# main_board.net
KiCad netlist of a schematic drawn in EAGLE
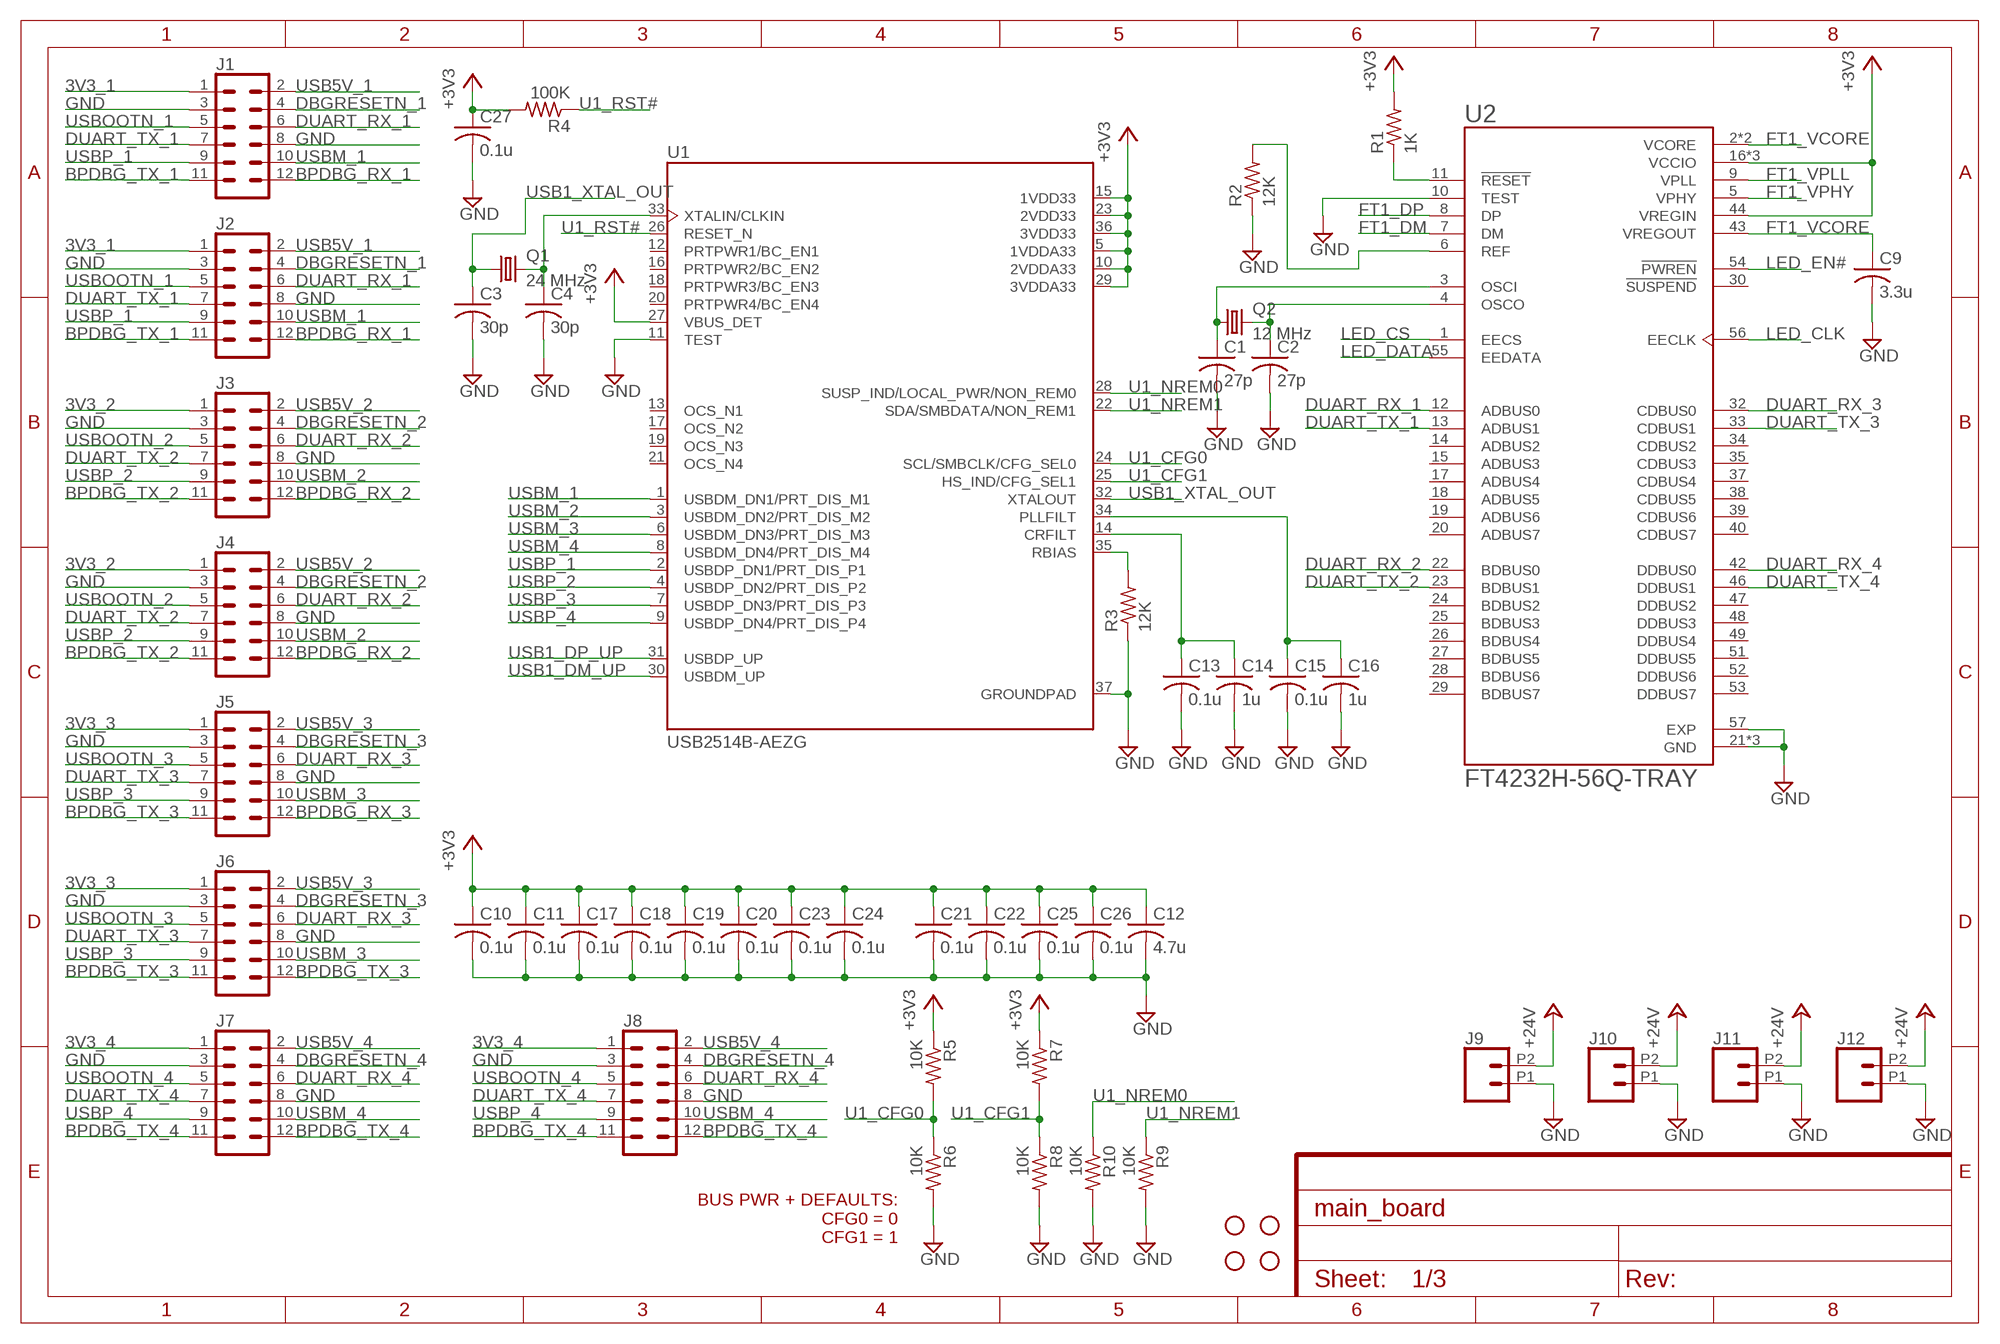
[diagram p0: schematic, sheet 1]
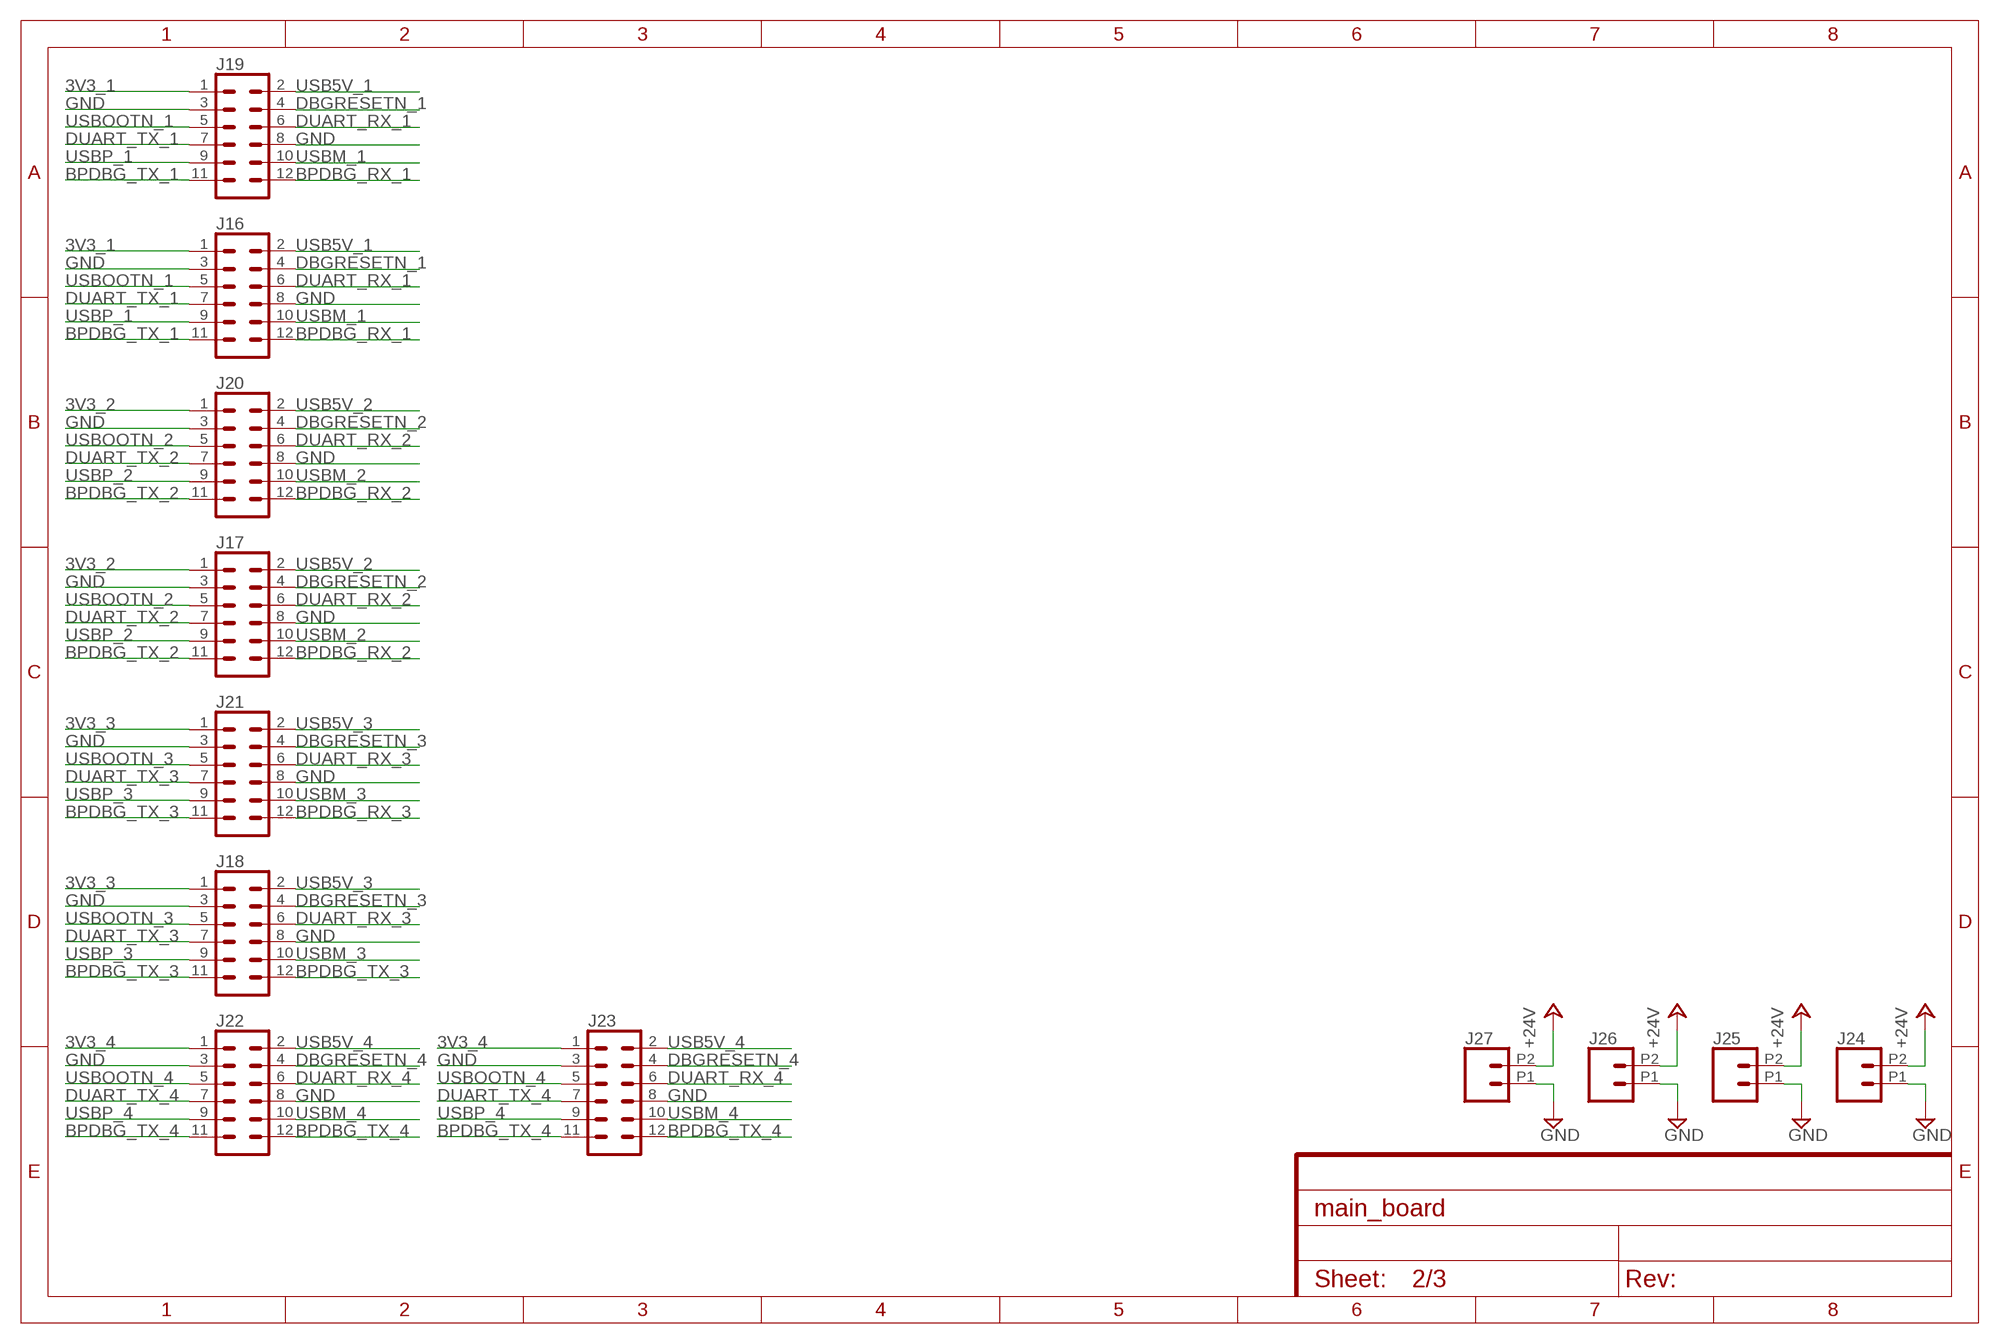
[diagram p1: schematic, sheet 2]
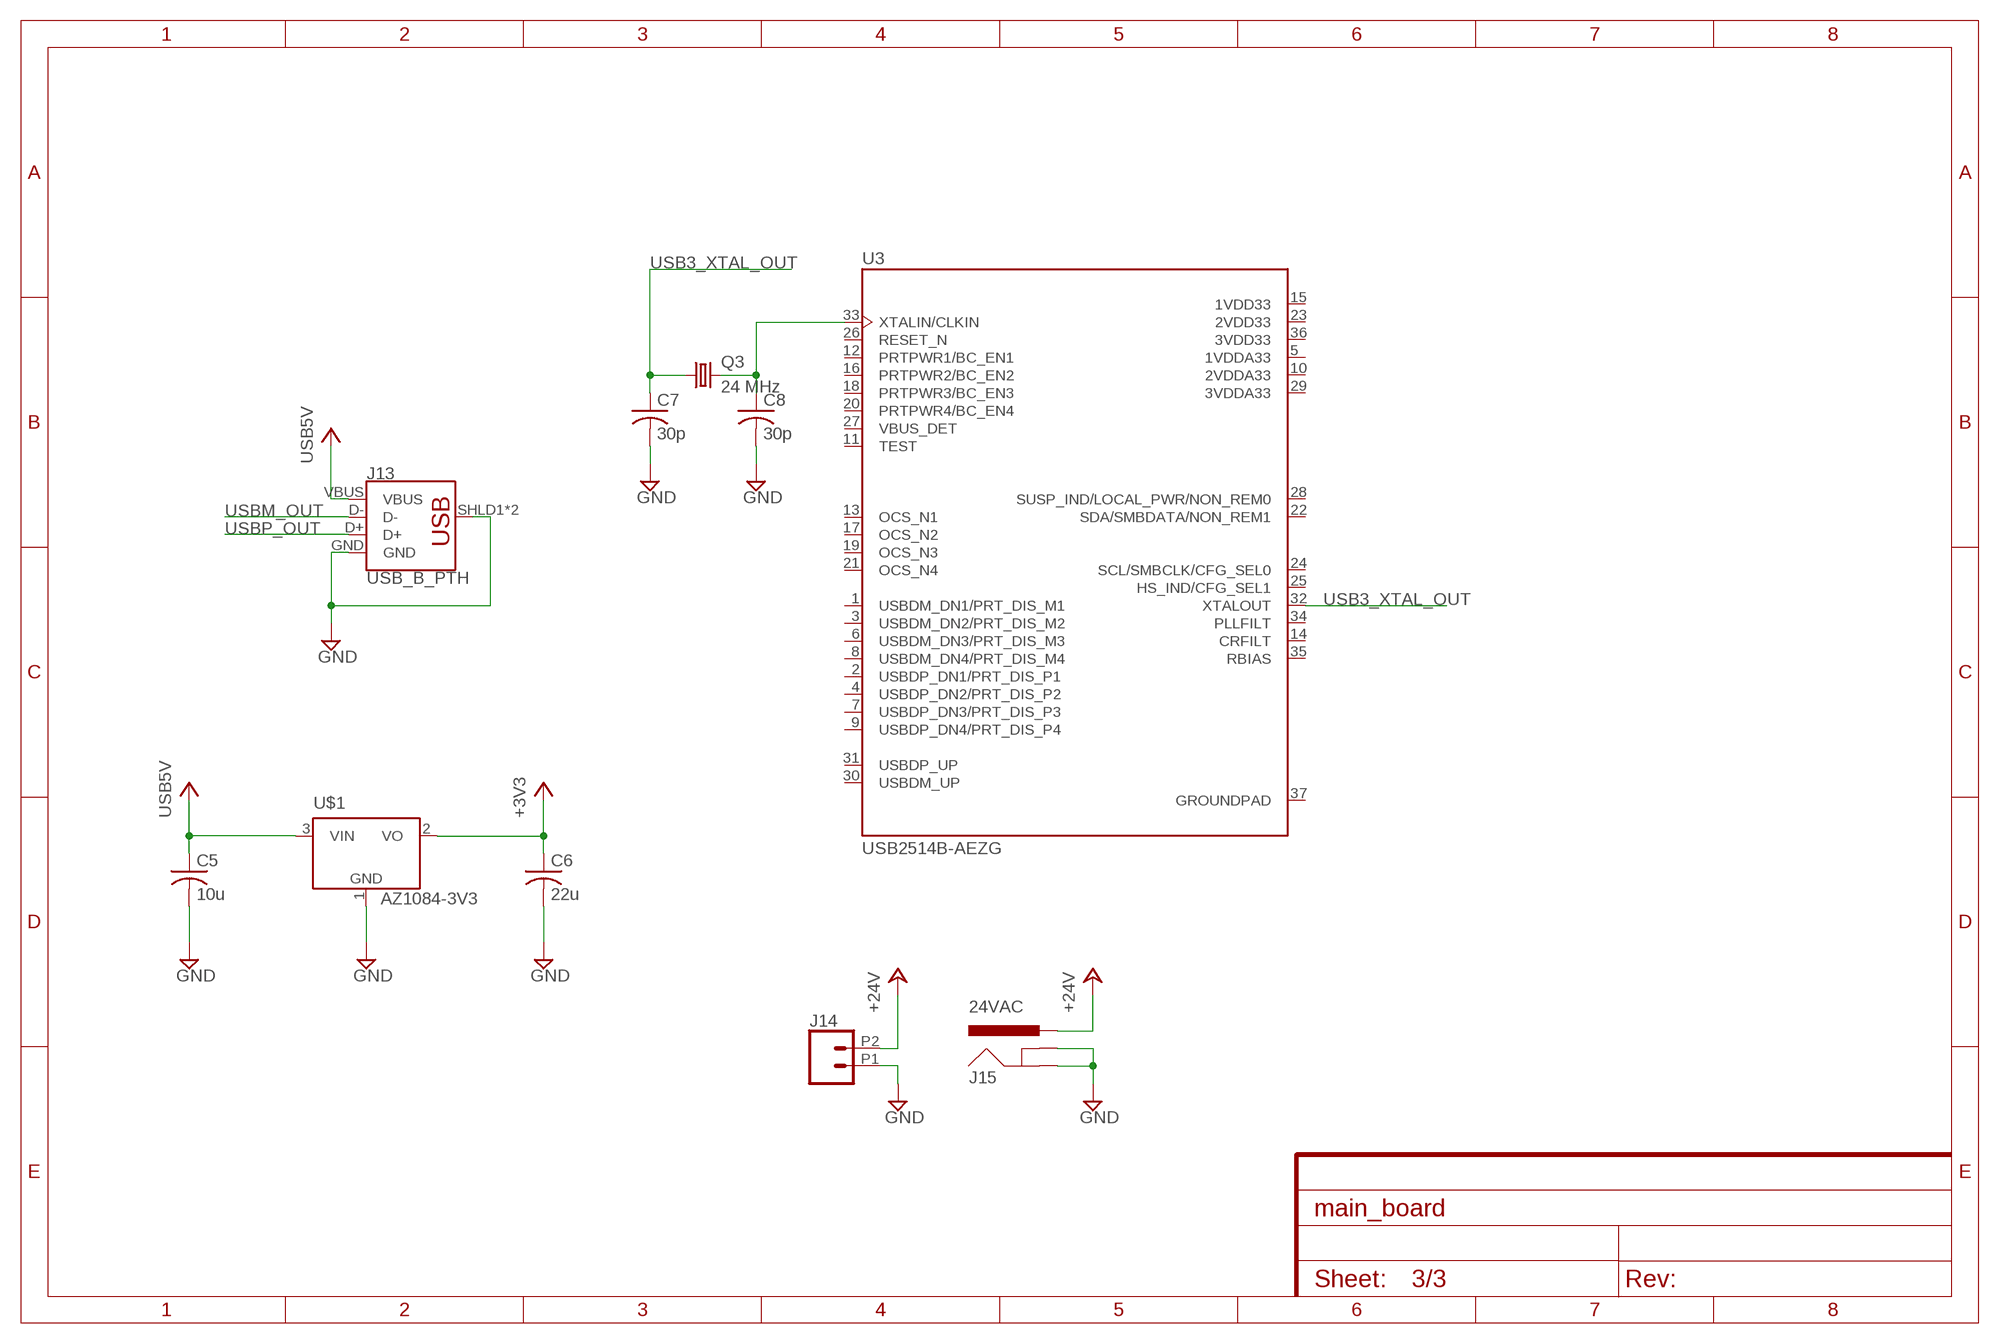
[diagram p2: schematic, sheet 3]

(export (version "E")
  (design (tool "Eeschema 10.0.6"))
  (components
    (comp (ref "J16")
      (value "CONN_06X2")
      (footprint "eagle-import:1X06_1.27MM")
      (libsource (lib "eagle-import") (part "CONN_06X2"))
    )
    (comp (ref "J17")
      (value "CONN_06X2")
      (footprint "eagle-import:1X06_1.27MM")
      (libsource (lib "eagle-import") (part "CONN_06X2"))
    )
    (comp (ref "J18")
      (value "CONN_06X2")
      (footprint "eagle-import:1X06_1.27MM")
      (libsource (lib "eagle-import") (part "CONN_06X2"))
    )
    (comp (ref "J19")
      (value "CONN_06X2")
      (footprint "eagle-import:1X06_1.27MM")
      (libsource (lib "eagle-import") (part "CONN_06X2"))
    )
    (comp (ref "J20")
      (value "CONN_06X2")
      (footprint "eagle-import:1X06_1.27MM")
      (libsource (lib "eagle-import") (part "CONN_06X2"))
    )
    (comp (ref "J21")
      (value "CONN_06X2")
      (footprint "eagle-import:1X06_1.27MM")
      (libsource (lib "eagle-import") (part "CONN_06X2"))
    )
    (comp (ref "J22")
      (value "CONN_06X2")
      (footprint "eagle-import:1X06_1.27MM")
      (libsource (lib "eagle-import") (part "CONN_06X2"))
    )
    (comp (ref "J23")
      (value "CONN_06X2")
      (footprint "eagle-import:1X06_1.27MM")
      (libsource (lib "eagle-import") (part "CONN_06X2"))
    )
    (comp (ref "J24")
      (value "CONN_022.54MM_SCREWTERM")
      (footprint "eagle-import:1X02_2.54_SCREWTERM")
      (libsource (lib "eagle-import") (part "CONN_022.54MM_SCREWTERM"))
    )
    (comp (ref "J25")
      (value "CONN_022.54MM_SCREWTERM")
      (footprint "eagle-import:1X02_2.54_SCREWTERM")
      (libsource (lib "eagle-import") (part "CONN_022.54MM_SCREWTERM"))
    )
    (comp (ref "J26")
      (value "CONN_022.54MM_SCREWTERM")
      (footprint "eagle-import:1X02_2.54_SCREWTERM")
      (libsource (lib "eagle-import") (part "CONN_022.54MM_SCREWTERM"))
    )
    (comp (ref "J27")
      (value "CONN_022.54MM_SCREWTERM")
      (footprint "eagle-import:1X02_2.54_SCREWTERM")
      (libsource (lib "eagle-import") (part "CONN_022.54MM_SCREWTERM"))
    )
    (comp (ref "C1")
      (value "27p")
      (footprint "eagle-import:C0805K")
      (libsource (lib "eagle-import") (part "C-USC0805K"))
    )
    (comp (ref "C2")
      (value "27p")
      (footprint "eagle-import:C0805K")
      (libsource (lib "eagle-import") (part "C-USC0805K"))
    )
    (comp (ref "C3")
      (value "30p")
      (footprint "eagle-import:C0805K")
      (libsource (lib "eagle-import") (part "C-USC0805K"))
    )
    (comp (ref "C4")
      (value "30p")
      (footprint "eagle-import:C0805K")
      (libsource (lib "eagle-import") (part "C-USC0805K"))
    )
    (comp (ref "C9")
      (value "3.3u")
      (footprint "eagle-import:C0805K")
      (libsource (lib "eagle-import") (part "C-USC0805K"))
    )
    (comp (ref "C10")
      (value "0.1u")
      (footprint "eagle-import:C0805K")
      (libsource (lib "eagle-import") (part "C-USC0805K"))
    )
    (comp (ref "C11")
      (value "0.1u")
      (footprint "eagle-import:C0805K")
      (libsource (lib "eagle-import") (part "C-USC0805K"))
    )
    (comp (ref "C12")
      (value "4.7u")
      (footprint "eagle-import:C0805K")
      (libsource (lib "eagle-import") (part "C-USC0805K"))
    )
    (comp (ref "C13")
      (value "0.1u")
      (footprint "eagle-import:C0805K")
      (libsource (lib "eagle-import") (part "C-USC0805K"))
    )
    (comp (ref "C14")
      (value "1u")
      (footprint "eagle-import:C0805K")
      (libsource (lib "eagle-import") (part "C-USC0805K"))
    )
    (comp (ref "C15")
      (value "0.1u")
      (footprint "eagle-import:C0805K")
      (libsource (lib "eagle-import") (part "C-USC0805K"))
    )
    (comp (ref "C16")
      (value "1u")
      (footprint "eagle-import:C0805K")
      (libsource (lib "eagle-import") (part "C-USC0805K"))
    )
    (comp (ref "C17")
      (value "0.1u")
      (footprint "eagle-import:C0805K")
      (libsource (lib "eagle-import") (part "C-USC0805K"))
    )
    (comp (ref "C18")
      (value "0.1u")
      (footprint "eagle-import:C0805K")
      (libsource (lib "eagle-import") (part "C-USC0805K"))
    )
    (comp (ref "C19")
      (value "0.1u")
      (footprint "eagle-import:C0805K")
      (libsource (lib "eagle-import") (part "C-USC0805K"))
    )
    (comp (ref "C20")
      (value "0.1u")
      (footprint "eagle-import:C0805K")
      (libsource (lib "eagle-import") (part "C-USC0805K"))
    )
    (comp (ref "C21")
      (value "0.1u")
      (footprint "eagle-import:C0805K")
      (libsource (lib "eagle-import") (part "C-USC0805K"))
    )
    (comp (ref "C22")
      (value "0.1u")
      (footprint "eagle-import:C0805K")
      (libsource (lib "eagle-import") (part "C-USC0805K"))
    )
    (comp (ref "C23")
      (value "0.1u")
      (footprint "eagle-import:C0805K")
      (libsource (lib "eagle-import") (part "C-USC0805K"))
    )
    (comp (ref "C24")
      (value "0.1u")
      (footprint "eagle-import:C0805K")
      (libsource (lib "eagle-import") (part "C-USC0805K"))
    )
    (comp (ref "C25")
      (value "0.1u")
      (footprint "eagle-import:C0805K")
      (libsource (lib "eagle-import") (part "C-USC0805K"))
    )
    (comp (ref "C26")
      (value "0.1u")
      (footprint "eagle-import:C0805K")
      (libsource (lib "eagle-import") (part "C-USC0805K"))
    )
    (comp (ref "C27")
      (value "0.1u")
      (footprint "eagle-import:C0805K")
      (libsource (lib "eagle-import") (part "C-USC0805K"))
    )
    (comp (ref "H1")
      (value "STAND-OFF")
      (footprint "eagle-import:STAND-OFF")
      (libsource (lib "eagle-import") (part "STAND-OFF"))
    )
    (comp (ref "H2")
      (value "STAND-OFF")
      (footprint "eagle-import:STAND-OFF")
      (libsource (lib "eagle-import") (part "STAND-OFF"))
    )
    (comp (ref "H3")
      (value "STAND-OFF")
      (footprint "eagle-import:STAND-OFF")
      (libsource (lib "eagle-import") (part "STAND-OFF"))
    )
    (comp (ref "H4")
      (value "STAND-OFF")
      (footprint "eagle-import:STAND-OFF")
      (libsource (lib "eagle-import") (part "STAND-OFF"))
    )
    (comp (ref "J1")
      (value "CONN_06X2")
      (footprint "eagle-import:1X06_1.27MM")
      (libsource (lib "eagle-import") (part "CONN_06X2"))
    )
    (comp (ref "J2")
      (value "CONN_06X2")
      (footprint "eagle-import:1X06_1.27MM")
      (libsource (lib "eagle-import") (part "CONN_06X2"))
    )
    (comp (ref "J3")
      (value "CONN_06X2")
      (footprint "eagle-import:1X06_1.27MM")
      (libsource (lib "eagle-import") (part "CONN_06X2"))
    )
    (comp (ref "J4")
      (value "CONN_06X2")
      (footprint "eagle-import:1X06_1.27MM")
      (libsource (lib "eagle-import") (part "CONN_06X2"))
    )
    (comp (ref "J5")
      (value "CONN_06X2")
      (footprint "eagle-import:1X06_1.27MM")
      (libsource (lib "eagle-import") (part "CONN_06X2"))
    )
    (comp (ref "J6")
      (value "CONN_06X2")
      (footprint "eagle-import:1X06_1.27MM")
      (libsource (lib "eagle-import") (part "CONN_06X2"))
    )
    (comp (ref "J7")
      (value "CONN_06X2")
      (footprint "eagle-import:1X06_1.27MM")
      (libsource (lib "eagle-import") (part "CONN_06X2"))
    )
    (comp (ref "J8")
      (value "CONN_06X2")
      (footprint "eagle-import:1X06_1.27MM")
      (libsource (lib "eagle-import") (part "CONN_06X2"))
    )
    (comp (ref "J9")
      (value "CONN_022.54MM_SCREWTERM")
      (footprint "eagle-import:1X02_2.54_SCREWTERM")
      (libsource (lib "eagle-import") (part "CONN_022.54MM_SCREWTERM"))
    )
    (comp (ref "J10")
      (value "CONN_022.54MM_SCREWTERM")
      (footprint "eagle-import:1X02_2.54_SCREWTERM")
      (libsource (lib "eagle-import") (part "CONN_022.54MM_SCREWTERM"))
    )
    (comp (ref "J11")
      (value "CONN_022.54MM_SCREWTERM")
      (footprint "eagle-import:1X02_2.54_SCREWTERM")
      (libsource (lib "eagle-import") (part "CONN_022.54MM_SCREWTERM"))
    )
    (comp (ref "J12")
      (value "CONN_022.54MM_SCREWTERM")
      (footprint "eagle-import:1X02_2.54_SCREWTERM")
      (libsource (lib "eagle-import") (part "CONN_022.54MM_SCREWTERM"))
    )
    (comp (ref "Q1")
      (value "24 MHz")
      (footprint "eagle-import:HC49UP")
      (libsource (lib "eagle-import") (part "CRYSTALHC49UP"))
    )
    (comp (ref "Q2")
      (value "12 MHz")
      (footprint "eagle-import:HC49UP")
      (libsource (lib "eagle-import") (part "CRYSTALHC49UP"))
    )
    (comp (ref "R1")
      (value "1K")
      (footprint "eagle-import:R0805")
      (libsource (lib "eagle-import") (part "R-US_R0805"))
    )
    (comp (ref "R2")
      (value "12K")
      (footprint "eagle-import:R0805")
      (libsource (lib "eagle-import") (part "R-US_R0805"))
    )
    (comp (ref "R3")
      (value "12K")
      (footprint "eagle-import:R0805")
      (libsource (lib "eagle-import") (part "R-US_R0805"))
    )
    (comp (ref "R4")
      (value "100K")
      (footprint "eagle-import:R0805")
      (libsource (lib "eagle-import") (part "R-US_R0805"))
    )
    (comp (ref "R5")
      (value "10K")
      (footprint "eagle-import:R0805")
      (libsource (lib "eagle-import") (part "R-US_R0805"))
    )
    (comp (ref "R6")
      (value "10K")
      (footprint "eagle-import:R0805")
      (libsource (lib "eagle-import") (part "R-US_R0805"))
    )
    (comp (ref "R7")
      (value "10K")
      (footprint "eagle-import:R0805")
      (libsource (lib "eagle-import") (part "R-US_R0805"))
    )
    (comp (ref "R8")
      (value "10K")
      (footprint "eagle-import:R0805")
      (libsource (lib "eagle-import") (part "R-US_R0805"))
    )
    (comp (ref "R9")
      (value "10K")
      (footprint "eagle-import:R0805")
      (libsource (lib "eagle-import") (part "R-US_R0805"))
    )
    (comp (ref "R10")
      (value "10K")
      (footprint "eagle-import:R0805")
      (libsource (lib "eagle-import") (part "R-US_R0805"))
    )
    (comp (ref "U1")
      (value "USB2514B-AEZG")
      (footprint "eagle-import:VQFN50P600X600X100-36N")
      (fields (field (name "MF") "Microchip"))
      (libsource (lib "eagle-import") (part "USB2514B-AEZG"))
    )
    (comp (ref "U2")
      (value "FT4232H-56Q-TRAY")
      (footprint "eagle-import:QFN50P800X800X100-57N")
      (fields (field (name "MF") "FTDI,"))
      (libsource (lib "eagle-import") (part "FT4232H-56Q-TRAY"))
    )
    (comp (ref "C5")
      (value "10u")
      (footprint "eagle-import:C0805K")
      (libsource (lib "eagle-import") (part "C-USC0805K"))
    )
    (comp (ref "C6")
      (value "22u")
      (footprint "eagle-import:C0805K")
      (libsource (lib "eagle-import") (part "C-USC0805K"))
    )
    (comp (ref "C7")
      (value "30p")
      (footprint "eagle-import:C0805K")
      (libsource (lib "eagle-import") (part "C-USC0805K"))
    )
    (comp (ref "C8")
      (value "30p")
      (footprint "eagle-import:C0805K")
      (libsource (lib "eagle-import") (part "C-USC0805K"))
    )
    (comp (ref "J13")
      (value "USB_B_PTH")
      (footprint "eagle-import:USB-B-PTH")
      (libsource (lib "eagle-import") (part "USB_B_PTH"))
    )
    (comp (ref "J14")
      (value "CONN_022.54MM_SCREWTERM")
      (footprint "eagle-import:1X02_2.54_SCREWTERM")
      (libsource (lib "eagle-import") (part "CONN_022.54MM_SCREWTERM"))
    )
    (comp (ref "J15")
      (value "24VAC")
      (footprint "eagle-import:POWER_JACK_SMD")
      (libsource (lib "eagle-import") (part "POWER_JACKSMD"))
    )
    (comp (ref "Q3")
      (value "24 MHz")
      (footprint "eagle-import:HC49UP")
      (libsource (lib "eagle-import") (part "CRYSTALHC49UP"))
    )
    (comp (ref "U$1")
      (value "AZ1084-3V3")
      (footprint "eagle-import:TO254P1435X457-4N")
      (libsource (lib "eagle-import") (part "AZ1084-3V3TO-263"))
    )
    (comp (ref "U3")
      (value "USB2514B-AEZG")
      (footprint "eagle-import:VQFN50P600X600X100-36N")
      (fields (field (name "MF") "Microchip"))
      (libsource (lib "eagle-import") (part "USB2514B-AEZG"))
    )
  )
  (nets
    (net (code "1") (name "+3V3") (class "Default")
      (node (ref "C10") (pin "1") (pinfunction "1_1") (pintype "passive"))
      (node (ref "C11") (pin "1") (pinfunction "1_1") (pintype "passive"))
      (node (ref "C12") (pin "1") (pinfunction "1_1") (pintype "passive"))
      (node (ref "C17") (pin "1") (pinfunction "1_1") (pintype "passive"))
      (node (ref "C18") (pin "1") (pinfunction "1_1") (pintype "passive"))
      (node (ref "C19") (pin "1") (pinfunction "1_1") (pintype "passive"))
      (node (ref "C20") (pin "1") (pinfunction "1_1") (pintype "passive"))
      (node (ref "C21") (pin "1") (pinfunction "1_1") (pintype "passive"))
      (node (ref "C22") (pin "1") (pinfunction "1_1") (pintype "passive"))
      (node (ref "C23") (pin "1") (pinfunction "1_1") (pintype "passive"))
      (node (ref "C24") (pin "1") (pinfunction "1_1") (pintype "passive"))
      (node (ref "C25") (pin "1") (pinfunction "1_1") (pintype "passive"))
      (node (ref "C26") (pin "1") (pinfunction "1_1") (pintype "passive"))
      (node (ref "C27") (pin "1") (pinfunction "1_1") (pintype "passive"))
      (node (ref "C6") (pin "1") (pinfunction "1_1") (pintype "passive"))
      (node (ref "R1") (pin "2") (pinfunction "2_2") (pintype "passive"))
      (node (ref "R4") (pin "2") (pinfunction "2_2") (pintype "passive"))
      (node (ref "R5") (pin "1") (pinfunction "1_1") (pintype "passive"))
      (node (ref "R7") (pin "1") (pinfunction "1_1") (pintype "passive"))
      (node (ref "U$1") (pin "2") (pinfunction "VO_2") (pintype "passive"))
      (node (ref "U1") (pin "10") (pinfunction "2VDDA33_10") (pintype "power_in"))
      (node (ref "U1") (pin "15") (pinfunction "1VDD33_15") (pintype "power_in"))
      (node (ref "U1") (pin "23") (pinfunction "2VDD33_23") (pintype "power_in"))
      (node (ref "U1") (pin "27") (pinfunction "VBUS_DET_27") (pintype "input"))
      (node (ref "U1") (pin "29") (pinfunction "3VDDA33_29") (pintype "output"))
      (node (ref "U1") (pin "36") (pinfunction "3VDD33_36") (pintype "power_in"))
      (node (ref "U1") (pin "5") (pinfunction "1VDDA33_5") (pintype "power_in"))
      (node (ref "U2") (pin "16") (pinfunction "VCCIO_16") (pintype "power_in"))
      (node (ref "U2") (pin "36") (pinfunction "VCCIO_36") (pintype "power_in"))
      (node (ref "U2") (pin "44") (pinfunction "VREGIN_44") (pintype "power_in"))
      (node (ref "U2") (pin "50") (pinfunction "VCCIO_50") (pintype "power_in"))
    )
    (net (code "2") (name "+5V") (class "Default")
      (node (ref "C5") (pin "1") (pinfunction "1_1") (pintype "passive"))
      (node (ref "J13") (pin "VBUS") (pinfunction "VBUS_VBUS") (pintype "power_in"))
      (node (ref "U$1") (pin "3") (pinfunction "VIN_3") (pintype "input"))
    )
    (net (code "3") (name "+24V") (class "Default")
      (node (ref "J10") (pin "P2") (pinfunction "2_P2") (pintype "passive"))
      (node (ref "J11") (pin "P2") (pinfunction "2_P2") (pintype "passive"))
      (node (ref "J12") (pin "P2") (pinfunction "2_P2") (pintype "passive"))
      (node (ref "J14") (pin "P2") (pinfunction "2_P2") (pintype "passive"))
      (node (ref "J15") (pin "VIN0") (pinfunction "PWR_VIN0") (pintype "bidirectional"))
      (node (ref "J24") (pin "P2") (pinfunction "2_P2") (pintype "passive"))
      (node (ref "J25") (pin "P2") (pinfunction "2_P2") (pintype "passive"))
      (node (ref "J26") (pin "P2") (pinfunction "2_P2") (pintype "passive"))
      (node (ref "J27") (pin "P2") (pinfunction "2_P2") (pintype "passive"))
      (node (ref "J9") (pin "P2") (pinfunction "2_P2") (pintype "passive"))
    )
    (net (code "4") (name "1VDD33") (class "Default")
      (node (ref "U3") (pin "15") (pinfunction "1VDD33_15") (pintype "power_in"))
    )
    (net (code "5") (name "1VDDA33") (class "Default")
      (node (ref "U3") (pin "5") (pinfunction "1VDDA33_5") (pintype "power_in"))
    )
    (net (code "6") (name "2VDD33") (class "Default")
      (node (ref "U3") (pin "23") (pinfunction "2VDD33_23") (pintype "power_in"))
    )
    (net (code "7") (name "2VDDA33") (class "Default")
      (node (ref "U3") (pin "10") (pinfunction "2VDDA33_10") (pintype "power_in"))
    )
    (net (code "8") (name "3V3_1") (class "Default")
      (node (ref "J1") (pin "1") (pinfunction "1_1") (pintype "passive"))
      (node (ref "J16") (pin "1") (pinfunction "1_1") (pintype "passive"))
      (node (ref "J19") (pin "1") (pinfunction "1_1") (pintype "passive"))
      (node (ref "J2") (pin "1") (pinfunction "1_1") (pintype "passive"))
    )
    (net (code "9") (name "3V3_2") (class "Default")
      (node (ref "J17") (pin "1") (pinfunction "1_1") (pintype "passive"))
      (node (ref "J20") (pin "1") (pinfunction "1_1") (pintype "passive"))
      (node (ref "J3") (pin "1") (pinfunction "1_1") (pintype "passive"))
      (node (ref "J4") (pin "1") (pinfunction "1_1") (pintype "passive"))
    )
    (net (code "10") (name "3V3_3") (class "Default")
      (node (ref "J18") (pin "1") (pinfunction "1_1") (pintype "passive"))
      (node (ref "J21") (pin "1") (pinfunction "1_1") (pintype "passive"))
      (node (ref "J5") (pin "1") (pinfunction "1_1") (pintype "passive"))
      (node (ref "J6") (pin "1") (pinfunction "1_1") (pintype "passive"))
    )
    (net (code "11") (name "3V3_4") (class "Default")
      (node (ref "J22") (pin "1") (pinfunction "1_1") (pintype "passive"))
      (node (ref "J23") (pin "1") (pinfunction "1_1") (pintype "passive"))
      (node (ref "J7") (pin "1") (pinfunction "1_1") (pintype "passive"))
      (node (ref "J8") (pin "1") (pinfunction "1_1") (pintype "passive"))
    )
    (net (code "12") (name "3VDD33") (class "Default")
      (node (ref "U3") (pin "36") (pinfunction "3VDD33_36") (pintype "power_in"))
    )
    (net (code "13") (name "BPDBG_RX_1") (class "Default")
      (node (ref "J1") (pin "12") (pinfunction "12_12") (pintype "passive"))
      (node (ref "J16") (pin "12") (pinfunction "12_12") (pintype "passive"))
      (node (ref "J19") (pin "12") (pinfunction "12_12") (pintype "passive"))
      (node (ref "J2") (pin "12") (pinfunction "12_12") (pintype "passive"))
    )
    (net (code "14") (name "BPDBG_RX_2") (class "Default")
      (node (ref "J17") (pin "12") (pinfunction "12_12") (pintype "passive"))
      (node (ref "J20") (pin "12") (pinfunction "12_12") (pintype "passive"))
      (node (ref "J3") (pin "12") (pinfunction "12_12") (pintype "passive"))
      (node (ref "J4") (pin "12") (pinfunction "12_12") (pintype "passive"))
    )
    (net (code "15") (name "BPDBG_RX_3") (class "Default")
      (node (ref "J21") (pin "12") (pinfunction "12_12") (pintype "passive"))
      (node (ref "J5") (pin "12") (pinfunction "12_12") (pintype "passive"))
    )
    (net (code "16") (name "BPDBG_TX_1") (class "Default")
      (node (ref "J1") (pin "11") (pinfunction "11_11") (pintype "passive"))
      (node (ref "J16") (pin "11") (pinfunction "11_11") (pintype "passive"))
      (node (ref "J19") (pin "11") (pinfunction "11_11") (pintype "passive"))
      (node (ref "J2") (pin "11") (pinfunction "11_11") (pintype "passive"))
    )
    (net (code "17") (name "BPDBG_TX_2") (class "Default")
      (node (ref "J17") (pin "11") (pinfunction "11_11") (pintype "passive"))
      (node (ref "J20") (pin "11") (pinfunction "11_11") (pintype "passive"))
      (node (ref "J3") (pin "11") (pinfunction "11_11") (pintype "passive"))
      (node (ref "J4") (pin "11") (pinfunction "11_11") (pintype "passive"))
    )
    (net (code "18") (name "BPDBG_TX_3") (class "Default")
      (node (ref "J18") (pin "11") (pinfunction "11_11") (pintype "passive"))
      (node (ref "J18") (pin "12") (pinfunction "12_12") (pintype "passive"))
      (node (ref "J21") (pin "11") (pinfunction "11_11") (pintype "passive"))
      (node (ref "J5") (pin "11") (pinfunction "11_11") (pintype "passive"))
      (node (ref "J6") (pin "11") (pinfunction "11_11") (pintype "passive"))
      (node (ref "J6") (pin "12") (pinfunction "12_12") (pintype "passive"))
    )
    (net (code "19") (name "BPDBG_TX_4") (class "Default")
      (node (ref "J22") (pin "11") (pinfunction "11_11") (pintype "passive"))
      (node (ref "J22") (pin "12") (pinfunction "12_12") (pintype "passive"))
      (node (ref "J23") (pin "11") (pinfunction "11_11") (pintype "passive"))
      (node (ref "J23") (pin "12") (pinfunction "12_12") (pintype "passive"))
      (node (ref "J7") (pin "11") (pinfunction "11_11") (pintype "passive"))
      (node (ref "J7") (pin "12") (pinfunction "12_12") (pintype "passive"))
      (node (ref "J8") (pin "11") (pinfunction "11_11") (pintype "passive"))
      (node (ref "J8") (pin "12") (pinfunction "12_12") (pintype "passive"))
    )
    (net (code "20") (name "DBGRESETN_1") (class "Default")
      (node (ref "J1") (pin "4") (pinfunction "4_4") (pintype "passive"))
      (node (ref "J16") (pin "4") (pinfunction "4_4") (pintype "passive"))
      (node (ref "J19") (pin "4") (pinfunction "4_4") (pintype "passive"))
      (node (ref "J2") (pin "4") (pinfunction "4_4") (pintype "passive"))
    )
    (net (code "21") (name "DBGRESETN_2") (class "Default")
      (node (ref "J17") (pin "4") (pinfunction "4_4") (pintype "passive"))
      (node (ref "J20") (pin "4") (pinfunction "4_4") (pintype "passive"))
      (node (ref "J3") (pin "4") (pinfunction "4_4") (pintype "passive"))
      (node (ref "J4") (pin "4") (pinfunction "4_4") (pintype "passive"))
    )
    (net (code "22") (name "DBGRESETN_3") (class "Default")
      (node (ref "J18") (pin "4") (pinfunction "4_4") (pintype "passive"))
      (node (ref "J21") (pin "4") (pinfunction "4_4") (pintype "passive"))
      (node (ref "J5") (pin "4") (pinfunction "4_4") (pintype "passive"))
      (node (ref "J6") (pin "4") (pinfunction "4_4") (pintype "passive"))
    )
    (net (code "23") (name "DBGRESETN_4") (class "Default")
      (node (ref "J22") (pin "4") (pinfunction "4_4") (pintype "passive"))
      (node (ref "J23") (pin "4") (pinfunction "4_4") (pintype "passive"))
      (node (ref "J7") (pin "4") (pinfunction "4_4") (pintype "passive"))
      (node (ref "J8") (pin "4") (pinfunction "4_4") (pintype "passive"))
    )
    (net (code "24") (name "DUART_RX_1") (class "Default")
      (node (ref "J1") (pin "6") (pinfunction "6_6") (pintype "passive"))
      (node (ref "J16") (pin "6") (pinfunction "6_6") (pintype "passive"))
      (node (ref "J19") (pin "6") (pinfunction "6_6") (pintype "passive"))
      (node (ref "J2") (pin "6") (pinfunction "6_6") (pintype "passive"))
      (node (ref "U2") (pin "12") (pinfunction "ADBUS0_12") (pintype "bidirectional"))
    )
    (net (code "25") (name "DUART_RX_2") (class "Default")
      (node (ref "J17") (pin "6") (pinfunction "6_6") (pintype "passive"))
      (node (ref "J20") (pin "6") (pinfunction "6_6") (pintype "passive"))
      (node (ref "J3") (pin "6") (pinfunction "6_6") (pintype "passive"))
      (node (ref "J4") (pin "6") (pinfunction "6_6") (pintype "passive"))
      (node (ref "U2") (pin "22") (pinfunction "BDBUS0_22") (pintype "bidirectional"))
    )
    (net (code "26") (name "DUART_RX_3") (class "Default")
      (node (ref "J18") (pin "6") (pinfunction "6_6") (pintype "passive"))
      (node (ref "J21") (pin "6") (pinfunction "6_6") (pintype "passive"))
      (node (ref "J5") (pin "6") (pinfunction "6_6") (pintype "passive"))
      (node (ref "J6") (pin "6") (pinfunction "6_6") (pintype "passive"))
      (node (ref "U2") (pin "32") (pinfunction "CDBUS0_32") (pintype "bidirectional"))
    )
    (net (code "27") (name "DUART_RX_4") (class "Default")
      (node (ref "J22") (pin "6") (pinfunction "6_6") (pintype "passive"))
      (node (ref "J23") (pin "6") (pinfunction "6_6") (pintype "passive"))
      (node (ref "J7") (pin "6") (pinfunction "6_6") (pintype "passive"))
      (node (ref "J8") (pin "6") (pinfunction "6_6") (pintype "passive"))
      (node (ref "U2") (pin "42") (pinfunction "DDBUS0_42") (pintype "bidirectional"))
    )
    (net (code "28") (name "DUART_TX_1") (class "Default")
      (node (ref "J1") (pin "7") (pinfunction "7_7") (pintype "passive"))
      (node (ref "J16") (pin "7") (pinfunction "7_7") (pintype "passive"))
      (node (ref "J19") (pin "7") (pinfunction "7_7") (pintype "passive"))
      (node (ref "J2") (pin "7") (pinfunction "7_7") (pintype "passive"))
      (node (ref "U2") (pin "13") (pinfunction "ADBUS1_13") (pintype "bidirectional"))
    )
    (net (code "29") (name "DUART_TX_2") (class "Default")
      (node (ref "J17") (pin "7") (pinfunction "7_7") (pintype "passive"))
      (node (ref "J20") (pin "7") (pinfunction "7_7") (pintype "passive"))
      (node (ref "J3") (pin "7") (pinfunction "7_7") (pintype "passive"))
      (node (ref "J4") (pin "7") (pinfunction "7_7") (pintype "passive"))
      (node (ref "U2") (pin "23") (pinfunction "BDBUS1_23") (pintype "bidirectional"))
    )
    (net (code "30") (name "DUART_TX_3") (class "Default")
      (node (ref "J18") (pin "7") (pinfunction "7_7") (pintype "passive"))
      (node (ref "J21") (pin "7") (pinfunction "7_7") (pintype "passive"))
      (node (ref "J5") (pin "7") (pinfunction "7_7") (pintype "passive"))
      (node (ref "J6") (pin "7") (pinfunction "7_7") (pintype "passive"))
      (node (ref "U2") (pin "33") (pinfunction "CDBUS1_33") (pintype "bidirectional"))
    )
    (net (code "31") (name "DUART_TX_4") (class "Default")
      (node (ref "J22") (pin "7") (pinfunction "7_7") (pintype "passive"))
      (node (ref "J23") (pin "7") (pinfunction "7_7") (pintype "passive"))
      (node (ref "J7") (pin "7") (pinfunction "7_7") (pintype "passive"))
      (node (ref "J8") (pin "7") (pinfunction "7_7") (pintype "passive"))
      (node (ref "U2") (pin "46") (pinfunction "DDBUS1_46") (pintype "bidirectional"))
    )
    (net (code "32") (name "FT1_DM") (class "Default")
      (node (ref "U2") (pin "7") (pinfunction "DM_7") (pintype "input"))
    )
    (net (code "33") (name "FT1_DP") (class "Default")
      (node (ref "U2") (pin "8") (pinfunction "DP_8") (pintype "input"))
    )
    (net (code "34") (name "FT1_VCORE") (class "Default")
      (node (ref "C9") (pin "1") (pinfunction "1_1") (pintype "passive"))
      (node (ref "U2") (pin "2") (pinfunction "VCORE_2") (pintype "power_in"))
      (node (ref "U2") (pin "31") (pinfunction "VCORE_31") (pintype "power_in"))
      (node (ref "U2") (pin "43") (pinfunction "VREGOUT_43") (pintype "power_in"))
    )
    (net (code "35") (name "FT1_VPHY") (class "Default")
      (node (ref "U2") (pin "5") (pinfunction "VPHY_5") (pintype "power_in"))
    )
    (net (code "36") (name "FT1_VPLL") (class "Default")
      (node (ref "U2") (pin "9") (pinfunction "VPLL_9") (pintype "power_in"))
    )
    (net (code "37") (name "GND") (class "Default")
      (node (ref "C1") (pin "2") (pinfunction "2_2") (pintype "passive"))
      (node (ref "C10") (pin "2") (pinfunction "2_2") (pintype "passive"))
      (node (ref "C11") (pin "2") (pinfunction "2_2") (pintype "passive"))
      (node (ref "C12") (pin "2") (pinfunction "2_2") (pintype "passive"))
      (node (ref "C13") (pin "2") (pinfunction "2_2") (pintype "passive"))
      (node (ref "C14") (pin "2") (pinfunction "2_2") (pintype "passive"))
      (node (ref "C15") (pin "2") (pinfunction "2_2") (pintype "passive"))
      (node (ref "C16") (pin "2") (pinfunction "2_2") (pintype "passive"))
      (node (ref "C17") (pin "2") (pinfunction "2_2") (pintype "passive"))
      (node (ref "C18") (pin "2") (pinfunction "2_2") (pintype "passive"))
      (node (ref "C19") (pin "2") (pinfunction "2_2") (pintype "passive"))
      (node (ref "C2") (pin "2") (pinfunction "2_2") (pintype "passive"))
      (node (ref "C20") (pin "2") (pinfunction "2_2") (pintype "passive"))
      (node (ref "C21") (pin "2") (pinfunction "2_2") (pintype "passive"))
      (node (ref "C22") (pin "2") (pinfunction "2_2") (pintype "passive"))
      (node (ref "C23") (pin "2") (pinfunction "2_2") (pintype "passive"))
      (node (ref "C24") (pin "2") (pinfunction "2_2") (pintype "passive"))
      (node (ref "C25") (pin "2") (pinfunction "2_2") (pintype "passive"))
      (node (ref "C26") (pin "2") (pinfunction "2_2") (pintype "passive"))
      (node (ref "C27") (pin "2") (pinfunction "2_2") (pintype "passive"))
      (node (ref "C3") (pin "2") (pinfunction "2_2") (pintype "passive"))
      (node (ref "C4") (pin "2") (pinfunction "2_2") (pintype "passive"))
      (node (ref "C5") (pin "2") (pinfunction "2_2") (pintype "passive"))
      (node (ref "C6") (pin "2") (pinfunction "2_2") (pintype "passive"))
      (node (ref "C7") (pin "2") (pinfunction "2_2") (pintype "passive"))
      (node (ref "C8") (pin "2") (pinfunction "2_2") (pintype "passive"))
      (node (ref "C9") (pin "2") (pinfunction "2_2") (pintype "passive"))
      (node (ref "J1") (pin "3") (pinfunction "3_3") (pintype "passive"))
      (node (ref "J1") (pin "8") (pinfunction "8_8") (pintype "passive"))
      (node (ref "J10") (pin "P1") (pinfunction "1_P1") (pintype "passive"))
      (node (ref "J11") (pin "P1") (pinfunction "1_P1") (pintype "passive"))
      (node (ref "J12") (pin "P1") (pinfunction "1_P1") (pintype "passive"))
      (node (ref "J13") (pin "GND") (pinfunction "GND_GND") (pintype "power_in"))
      (node (ref "J13") (pin "SHLD1") (pinfunction "SHIELD_SHLD1") (pintype "bidirectional"))
      (node (ref "J13") (pin "SHLD2") (pinfunction "SHIELD_SHLD2") (pintype "bidirectional"))
      (node (ref "J14") (pin "P1") (pinfunction "1_P1") (pintype "passive"))
      (node (ref "J15") (pin "GND") (pinfunction "GNDBREAK_GND") (pintype "bidirectional"))
      (node (ref "J15") (pin "P$4") (pinfunction "GND_P$4") (pintype "bidirectional"))
      (node (ref "J16") (pin "3") (pinfunction "3_3") (pintype "passive"))
      (node (ref "J16") (pin "8") (pinfunction "8_8") (pintype "passive"))
      (node (ref "J17") (pin "3") (pinfunction "3_3") (pintype "passive"))
      (node (ref "J17") (pin "8") (pinfunction "8_8") (pintype "passive"))
      (node (ref "J18") (pin "3") (pinfunction "3_3") (pintype "passive"))
      (node (ref "J18") (pin "8") (pinfunction "8_8") (pintype "passive"))
      (node (ref "J19") (pin "3") (pinfunction "3_3") (pintype "passive"))
      (node (ref "J19") (pin "8") (pinfunction "8_8") (pintype "passive"))
      (node (ref "J2") (pin "3") (pinfunction "3_3") (pintype "passive"))
      (node (ref "J2") (pin "8") (pinfunction "8_8") (pintype "passive"))
      (node (ref "J20") (pin "3") (pinfunction "3_3") (pintype "passive"))
      (node (ref "J20") (pin "8") (pinfunction "8_8") (pintype "passive"))
      (node (ref "J21") (pin "3") (pinfunction "3_3") (pintype "passive"))
      (node (ref "J21") (pin "8") (pinfunction "8_8") (pintype "passive"))
      (node (ref "J22") (pin "3") (pinfunction "3_3") (pintype "passive"))
      (node (ref "J22") (pin "8") (pinfunction "8_8") (pintype "passive"))
      (node (ref "J23") (pin "3") (pinfunction "3_3") (pintype "passive"))
      (node (ref "J23") (pin "8") (pinfunction "8_8") (pintype "passive"))
      (node (ref "J24") (pin "P1") (pinfunction "1_P1") (pintype "passive"))
      (node (ref "J25") (pin "P1") (pinfunction "1_P1") (pintype "passive"))
      (node (ref "J26") (pin "P1") (pinfunction "1_P1") (pintype "passive"))
      (node (ref "J27") (pin "P1") (pinfunction "1_P1") (pintype "passive"))
      (node (ref "J3") (pin "3") (pinfunction "3_3") (pintype "passive"))
      (node (ref "J3") (pin "8") (pinfunction "8_8") (pintype "passive"))
      (node (ref "J4") (pin "3") (pinfunction "3_3") (pintype "passive"))
      (node (ref "J4") (pin "8") (pinfunction "8_8") (pintype "passive"))
      (node (ref "J5") (pin "3") (pinfunction "3_3") (pintype "passive"))
      (node (ref "J5") (pin "8") (pinfunction "8_8") (pintype "passive"))
      (node (ref "J6") (pin "3") (pinfunction "3_3") (pintype "passive"))
      (node (ref "J6") (pin "8") (pinfunction "8_8") (pintype "passive"))
      (node (ref "J7") (pin "3") (pinfunction "3_3") (pintype "passive"))
      (node (ref "J7") (pin "8") (pinfunction "8_8") (pintype "passive"))
      (node (ref "J8") (pin "3") (pinfunction "3_3") (pintype "passive"))
      (node (ref "J8") (pin "8") (pinfunction "8_8") (pintype "passive"))
      (node (ref "J9") (pin "P1") (pinfunction "1_P1") (pintype "passive"))
      (node (ref "R10") (pin "2") (pinfunction "2_2") (pintype "passive"))
      (node (ref "R2") (pin "1") (pinfunction "1_1") (pintype "passive"))
      (node (ref "R3") (pin "1") (pinfunction "1_1") (pintype "passive"))
      (node (ref "R6") (pin "2") (pinfunction "2_2") (pintype "passive"))
      (node (ref "R8") (pin "2") (pinfunction "2_2") (pintype "passive"))
      (node (ref "R9") (pin "2") (pinfunction "2_2") (pintype "passive"))
      (node (ref "U$1") (pin "1") (pinfunction "GND_1") (pintype "passive"))
      (node (ref "U1") (pin "11") (pinfunction "TEST_11") (pintype "input"))
      (node (ref "U1") (pin "37") (pinfunction "GROUNDPAD_37") (pintype "power_in"))
      (node (ref "U2") (pin "10") (pinfunction "TEST_10") (pintype "input"))
      (node (ref "U2") (pin "21") (pinfunction "GND_21") (pintype "power_in"))
      (node (ref "U2") (pin "41") (pinfunction "GND_41") (pintype "power_in"))
      (node (ref "U2") (pin "45") (pinfunction "GND_45") (pintype "power_in"))
      (node (ref "U2") (pin "57") (pinfunction "EXP_57") (pintype "power_in"))
    )
    (net (code "38") (name "GROUNDPAD") (class "Default")
      (node (ref "U3") (pin "37") (pinfunction "GROUNDPAD_37") (pintype "power_in"))
    )
    (net (code "39") (name "LED_CLK") (class "Default")
      (node (ref "U2") (pin "56") (pinfunction "EECLK_56") (pintype "output"))
    )
    (net (code "40") (name "LED_CS") (class "Default")
      (node (ref "U2") (pin "1") (pinfunction "EECS_1") (pintype "bidirectional"))
    )
    (net (code "41") (name "LED_DATA") (class "Default")
      (node (ref "U2") (pin "55") (pinfunction "EEDATA_55") (pintype "bidirectional"))
    )
    (net (code "42") (name "LED_EN#") (class "Default")
      (node (ref "U2") (pin "54") (pinfunction "~{PWREN}_54") (pintype "output"))
    )
    (net (code "43") (name "Net-(U1-CRFILT)") (class "Default")
      (node (ref "C13") (pin "1") (pinfunction "1_1") (pintype "passive"))
      (node (ref "C14") (pin "1") (pinfunction "1_1") (pintype "passive"))
      (node (ref "U1") (pin "14") (pinfunction "CRFILT_14") (pintype "output"))
    )
    (net (code "44") (name "Net-(U1-PLLFILT)") (class "Default")
      (node (ref "C15") (pin "1") (pinfunction "1_1") (pintype "passive"))
      (node (ref "C16") (pin "1") (pinfunction "1_1") (pintype "passive"))
      (node (ref "U1") (pin "34") (pinfunction "PLLFILT_34") (pintype "output"))
    )
    (net (code "45") (name "Net-(U1-RBIAS)") (class "Default")
      (node (ref "R3") (pin "2") (pinfunction "2_2") (pintype "passive"))
      (node (ref "U1") (pin "35") (pinfunction "RBIAS_35") (pintype "output"))
    )
    (net (code "46") (name "Net-(U1-XTALIN{slash}CLKIN)") (class "Default")
      (node (ref "C4") (pin "1") (pinfunction "1_1") (pintype "passive"))
      (node (ref "Q1") (pin "2") (pinfunction "2_2") (pintype "passive"))
      (node (ref "U1") (pin "33") (pinfunction "XTALIN/CLKIN_33") (pintype "input"))
    )
    (net (code "47") (name "Net-(U2-OSCI)") (class "Default")
      (node (ref "C1") (pin "1") (pinfunction "1_1") (pintype "passive"))
      (node (ref "Q2") (pin "1") (pinfunction "1_1") (pintype "passive"))
      (node (ref "U2") (pin "3") (pinfunction "OSCI_3") (pintype "input"))
    )
    (net (code "48") (name "Net-(U2-OSCO)") (class "Default")
      (node (ref "C2") (pin "1") (pinfunction "1_1") (pintype "passive"))
      (node (ref "Q2") (pin "2") (pinfunction "2_2") (pintype "passive"))
      (node (ref "U2") (pin "4") (pinfunction "OSCO_4") (pintype "output"))
    )
    (net (code "49") (name "Net-(U2-REF)") (class "Default")
      (node (ref "R2") (pin "2") (pinfunction "2_2") (pintype "passive"))
      (node (ref "U2") (pin "6") (pinfunction "REF_6") (pintype "input"))
    )
    (net (code "50") (name "Net-(U2-~{RESET})") (class "Default")
      (node (ref "R1") (pin "1") (pinfunction "1_1") (pintype "passive"))
      (node (ref "U2") (pin "11") (pinfunction "~{RESET}_11") (pintype "input"))
    )
    (net (code "51") (name "Net-(U3-XTALIN{slash}CLKIN)") (class "Default")
      (node (ref "C8") (pin "1") (pinfunction "1_1") (pintype "passive"))
      (node (ref "Q3") (pin "2") (pinfunction "2_2") (pintype "passive"))
      (node (ref "U3") (pin "33") (pinfunction "XTALIN/CLKIN_33") (pintype "input"))
    )
    (net (code "52") (name "U1_CFG0") (class "Default")
      (node (ref "R5") (pin "2") (pinfunction "2_2") (pintype "passive"))
      (node (ref "R6") (pin "1") (pinfunction "1_1") (pintype "passive"))
      (node (ref "U1") (pin "24") (pinfunction "SCL/SMBCLK/CFG_SEL0_24") (pintype "output"))
    )
    (net (code "53") (name "U1_CFG1") (class "Default")
      (node (ref "R7") (pin "2") (pinfunction "2_2") (pintype "passive"))
      (node (ref "R8") (pin "1") (pinfunction "1_1") (pintype "passive"))
      (node (ref "U1") (pin "25") (pinfunction "HS_IND/CFG_SEL1_25") (pintype "output"))
    )
    (net (code "54") (name "U1_NREM0") (class "Default")
      (node (ref "R10") (pin "1") (pinfunction "1_1") (pintype "passive"))
      (node (ref "U1") (pin "28") (pinfunction "SUSP_IND/LOCAL_PWR/NON_REM0_28") (pintype "bidirectional"))
    )
    (net (code "55") (name "U1_NREM1") (class "Default")
      (node (ref "R9") (pin "1") (pinfunction "1_1") (pintype "passive"))
      (node (ref "U1") (pin "22") (pinfunction "SDA/SMBDATA/NON_REM1_22") (pintype "bidirectional"))
    )
    (net (code "56") (name "U1_RST#") (class "Default")
      (node (ref "R4") (pin "1") (pinfunction "1_1") (pintype "passive"))
      (node (ref "U1") (pin "26") (pinfunction "RESET_N_26") (pintype "input"))
    )
    (net (code "57") (name "USB1_DM_UP") (class "Default")
      (node (ref "U1") (pin "30") (pinfunction "USBDM_UP_30") (pintype "bidirectional"))
    )
    (net (code "58") (name "USB1_DP_UP") (class "Default")
      (node (ref "U1") (pin "31") (pinfunction "USBDP_UP_31") (pintype "bidirectional"))
    )
    (net (code "59") (name "USB1_XTAL_OUT") (class "Default")
      (node (ref "C3") (pin "1") (pinfunction "1_1") (pintype "passive"))
      (node (ref "Q1") (pin "1") (pinfunction "1_1") (pintype "passive"))
      (node (ref "U1") (pin "32") (pinfunction "XTALOUT_32") (pintype "output"))
    )
    (net (code "60") (name "USB3_XTAL_OUT") (class "Default")
      (node (ref "C7") (pin "1") (pinfunction "1_1") (pintype "passive"))
      (node (ref "Q3") (pin "1") (pinfunction "1_1") (pintype "passive"))
      (node (ref "U3") (pin "32") (pinfunction "XTALOUT_32") (pintype "output"))
    )
    (net (code "61") (name "USB5V_1") (class "Default")
      (node (ref "J1") (pin "2") (pinfunction "2_2") (pintype "passive"))
      (node (ref "J16") (pin "2") (pinfunction "2_2") (pintype "passive"))
      (node (ref "J19") (pin "2") (pinfunction "2_2") (pintype "passive"))
      (node (ref "J2") (pin "2") (pinfunction "2_2") (pintype "passive"))
    )
    (net (code "62") (name "USB5V_2") (class "Default")
      (node (ref "J17") (pin "2") (pinfunction "2_2") (pintype "passive"))
      (node (ref "J20") (pin "2") (pinfunction "2_2") (pintype "passive"))
      (node (ref "J3") (pin "2") (pinfunction "2_2") (pintype "passive"))
      (node (ref "J4") (pin "2") (pinfunction "2_2") (pintype "passive"))
    )
    (net (code "63") (name "USB5V_3") (class "Default")
      (node (ref "J18") (pin "2") (pinfunction "2_2") (pintype "passive"))
      (node (ref "J21") (pin "2") (pinfunction "2_2") (pintype "passive"))
      (node (ref "J5") (pin "2") (pinfunction "2_2") (pintype "passive"))
      (node (ref "J6") (pin "2") (pinfunction "2_2") (pintype "passive"))
    )
    (net (code "64") (name "USB5V_4") (class "Default")
      (node (ref "J22") (pin "2") (pinfunction "2_2") (pintype "passive"))
      (node (ref "J23") (pin "2") (pinfunction "2_2") (pintype "passive"))
      (node (ref "J7") (pin "2") (pinfunction "2_2") (pintype "passive"))
      (node (ref "J8") (pin "2") (pinfunction "2_2") (pintype "passive"))
    )
    (net (code "65") (name "USBM_1") (class "Default")
      (node (ref "J1") (pin "10") (pinfunction "10_10") (pintype "passive"))
      (node (ref "J16") (pin "10") (pinfunction "10_10") (pintype "passive"))
      (node (ref "J19") (pin "10") (pinfunction "10_10") (pintype "passive"))
      (node (ref "J2") (pin "10") (pinfunction "10_10") (pintype "passive"))
      (node (ref "U1") (pin "1") (pinfunction "USBDM_DN1/PRT_DIS_M1_1") (pintype "bidirectional"))
    )
    (net (code "66") (name "USBM_2") (class "Default")
      (node (ref "J17") (pin "10") (pinfunction "10_10") (pintype "passive"))
      (node (ref "J20") (pin "10") (pinfunction "10_10") (pintype "passive"))
      (node (ref "J3") (pin "10") (pinfunction "10_10") (pintype "passive"))
      (node (ref "J4") (pin "10") (pinfunction "10_10") (pintype "passive"))
      (node (ref "U1") (pin "3") (pinfunction "USBDM_DN2/PRT_DIS_M2_3") (pintype "bidirectional"))
    )
    (net (code "67") (name "USBM_3") (class "Default")
      (node (ref "J18") (pin "10") (pinfunction "10_10") (pintype "passive"))
      (node (ref "J21") (pin "10") (pinfunction "10_10") (pintype "passive"))
      (node (ref "J5") (pin "10") (pinfunction "10_10") (pintype "passive"))
      (node (ref "J6") (pin "10") (pinfunction "10_10") (pintype "passive"))
      (node (ref "U1") (pin "6") (pinfunction "USBDM_DN3/PRT_DIS_M3_6") (pintype "bidirectional"))
    )
    (net (code "68") (name "USBM_4") (class "Default")
      (node (ref "J22") (pin "10") (pinfunction "10_10") (pintype "passive"))
      (node (ref "J23") (pin "10") (pinfunction "10_10") (pintype "passive"))
      (node (ref "J7") (pin "10") (pinfunction "10_10") (pintype "passive"))
      (node (ref "J8") (pin "10") (pinfunction "10_10") (pintype "passive"))
      (node (ref "U1") (pin "8") (pinfunction "USBDM_DN4/PRT_DIS_M4_8") (pintype "bidirectional"))
    )
    (net (code "69") (name "USBM_OUT") (class "Default")
      (node (ref "J13") (pin "D-") (pinfunction "D-_D-") (pintype "bidirectional"))
    )
    (net (code "70") (name "USBOOTN_1") (class "Default")
      (node (ref "J1") (pin "5") (pinfunction "5_5") (pintype "passive"))
      (node (ref "J16") (pin "5") (pinfunction "5_5") (pintype "passive"))
      (node (ref "J19") (pin "5") (pinfunction "5_5") (pintype "passive"))
      (node (ref "J2") (pin "5") (pinfunction "5_5") (pintype "passive"))
    )
    (net (code "71") (name "USBOOTN_2") (class "Default")
      (node (ref "J17") (pin "5") (pinfunction "5_5") (pintype "passive"))
      (node (ref "J20") (pin "5") (pinfunction "5_5") (pintype "passive"))
      (node (ref "J3") (pin "5") (pinfunction "5_5") (pintype "passive"))
      (node (ref "J4") (pin "5") (pinfunction "5_5") (pintype "passive"))
    )
    (net (code "72") (name "USBOOTN_3") (class "Default")
      (node (ref "J18") (pin "5") (pinfunction "5_5") (pintype "passive"))
      (node (ref "J21") (pin "5") (pinfunction "5_5") (pintype "passive"))
      (node (ref "J5") (pin "5") (pinfunction "5_5") (pintype "passive"))
      (node (ref "J6") (pin "5") (pinfunction "5_5") (pintype "passive"))
    )
    (net (code "73") (name "USBOOTN_4") (class "Default")
      (node (ref "J22") (pin "5") (pinfunction "5_5") (pintype "passive"))
      (node (ref "J23") (pin "5") (pinfunction "5_5") (pintype "passive"))
      (node (ref "J7") (pin "5") (pinfunction "5_5") (pintype "passive"))
      (node (ref "J8") (pin "5") (pinfunction "5_5") (pintype "passive"))
    )
    (net (code "74") (name "USBP_1") (class "Default")
      (node (ref "J1") (pin "9") (pinfunction "9_9") (pintype "passive"))
      (node (ref "J16") (pin "9") (pinfunction "9_9") (pintype "passive"))
      (node (ref "J19") (pin "9") (pinfunction "9_9") (pintype "passive"))
      (node (ref "J2") (pin "9") (pinfunction "9_9") (pintype "passive"))
      (node (ref "U1") (pin "2") (pinfunction "USBDP_DN1/PRT_DIS_P1_2") (pintype "bidirectional"))
    )
    (net (code "75") (name "USBP_2") (class "Default")
      (node (ref "J17") (pin "9") (pinfunction "9_9") (pintype "passive"))
      (node (ref "J20") (pin "9") (pinfunction "9_9") (pintype "passive"))
      (node (ref "J3") (pin "9") (pinfunction "9_9") (pintype "passive"))
      (node (ref "J4") (pin "9") (pinfunction "9_9") (pintype "passive"))
      (node (ref "U1") (pin "4") (pinfunction "USBDP_DN2/PRT_DIS_P2_4") (pintype "bidirectional"))
    )
    (net (code "76") (name "USBP_3") (class "Default")
      (node (ref "J18") (pin "9") (pinfunction "9_9") (pintype "passive"))
      (node (ref "J21") (pin "9") (pinfunction "9_9") (pintype "passive"))
      (node (ref "J5") (pin "9") (pinfunction "9_9") (pintype "passive"))
      (node (ref "J6") (pin "9") (pinfunction "9_9") (pintype "passive"))
      (node (ref "U1") (pin "7") (pinfunction "USBDP_DN3/PRT_DIS_P3_7") (pintype "bidirectional"))
    )
    (net (code "77") (name "USBP_4") (class "Default")
      (node (ref "J22") (pin "9") (pinfunction "9_9") (pintype "passive"))
      (node (ref "J23") (pin "9") (pinfunction "9_9") (pintype "passive"))
      (node (ref "J7") (pin "9") (pinfunction "9_9") (pintype "passive"))
      (node (ref "J8") (pin "9") (pinfunction "9_9") (pintype "passive"))
      (node (ref "U1") (pin "9") (pinfunction "USBDP_DN4/PRT_DIS_P4_9") (pintype "bidirectional"))
    )
    (net (code "78") (name "USBP_OUT") (class "Default")
      (node (ref "J13") (pin "D+") (pinfunction "D+_D+") (pintype "bidirectional"))
    )
    (net (code "79") (name "unconnected-(U1-OCS_N1-Pad13)") (class "Default")
      (node (ref "U1") (pin "13") (pinfunction "OCS_N1_13") (pintype "bidirectional"))
    )
    (net (code "80") (name "unconnected-(U1-OCS_N2-Pad17)") (class "Default")
      (node (ref "U1") (pin "17") (pinfunction "OCS_N2_17") (pintype "bidirectional"))
    )
    (net (code "81") (name "unconnected-(U1-OCS_N3-Pad19)") (class "Default")
      (node (ref "U1") (pin "19") (pinfunction "OCS_N3_19") (pintype "bidirectional"))
    )
    (net (code "82") (name "unconnected-(U1-OCS_N4-Pad21)") (class "Default")
      (node (ref "U1") (pin "21") (pinfunction "OCS_N4_21") (pintype "bidirectional"))
    )
    (net (code "83") (name "unconnected-(U1-PRTPWR1{slash}BC_EN1-Pad12)") (class "Default")
      (node (ref "U1") (pin "12") (pinfunction "PRTPWR1/BC_EN1_12") (pintype "input"))
    )
    (net (code "84") (name "unconnected-(U1-PRTPWR2{slash}BC_EN2-Pad16)") (class "Default")
      (node (ref "U1") (pin "16") (pinfunction "PRTPWR2/BC_EN2_16") (pintype "input"))
    )
    (net (code "85") (name "unconnected-(U1-PRTPWR3{slash}BC_EN3-Pad18)") (class "Default")
      (node (ref "U1") (pin "18") (pinfunction "PRTPWR3/BC_EN3_18") (pintype "input"))
    )
    (net (code "86") (name "unconnected-(U1-PRTPWR4{slash}BC_EN4-Pad20)") (class "Default")
      (node (ref "U1") (pin "20") (pinfunction "PRTPWR4/BC_EN4_20") (pintype "input"))
    )
    (net (code "87") (name "unconnected-(U2-ADBUS2-Pad14)") (class "Default")
      (node (ref "U2") (pin "14") (pinfunction "ADBUS2_14") (pintype "bidirectional"))
    )
    (net (code "88") (name "unconnected-(U2-ADBUS3-Pad15)") (class "Default")
      (node (ref "U2") (pin "15") (pinfunction "ADBUS3_15") (pintype "bidirectional"))
    )
    (net (code "89") (name "unconnected-(U2-ADBUS4-Pad17)") (class "Default")
      (node (ref "U2") (pin "17") (pinfunction "ADBUS4_17") (pintype "bidirectional"))
    )
    (net (code "90") (name "unconnected-(U2-ADBUS5-Pad18)") (class "Default")
      (node (ref "U2") (pin "18") (pinfunction "ADBUS5_18") (pintype "bidirectional"))
    )
    (net (code "91") (name "unconnected-(U2-ADBUS6-Pad19)") (class "Default")
      (node (ref "U2") (pin "19") (pinfunction "ADBUS6_19") (pintype "bidirectional"))
    )
    (net (code "92") (name "unconnected-(U2-ADBUS7-Pad20)") (class "Default")
      (node (ref "U2") (pin "20") (pinfunction "ADBUS7_20") (pintype "bidirectional"))
    )
    (net (code "93") (name "unconnected-(U2-BDBUS2-Pad24)") (class "Default")
      (node (ref "U2") (pin "24") (pinfunction "BDBUS2_24") (pintype "bidirectional"))
    )
    (net (code "94") (name "unconnected-(U2-BDBUS3-Pad25)") (class "Default")
      (node (ref "U2") (pin "25") (pinfunction "BDBUS3_25") (pintype "bidirectional"))
    )
    (net (code "95") (name "unconnected-(U2-BDBUS4-Pad26)") (class "Default")
      (node (ref "U2") (pin "26") (pinfunction "BDBUS4_26") (pintype "bidirectional"))
    )
    (net (code "96") (name "unconnected-(U2-BDBUS5-Pad27)") (class "Default")
      (node (ref "U2") (pin "27") (pinfunction "BDBUS5_27") (pintype "bidirectional"))
    )
    (net (code "97") (name "unconnected-(U2-BDBUS6-Pad28)") (class "Default")
      (node (ref "U2") (pin "28") (pinfunction "BDBUS6_28") (pintype "bidirectional"))
    )
    (net (code "98") (name "unconnected-(U2-BDBUS7-Pad29)") (class "Default")
      (node (ref "U2") (pin "29") (pinfunction "BDBUS7_29") (pintype "bidirectional"))
    )
    (net (code "99") (name "unconnected-(U2-CDBUS2-Pad34)") (class "Default")
      (node (ref "U2") (pin "34") (pinfunction "CDBUS2_34") (pintype "bidirectional"))
    )
    (net (code "100") (name "unconnected-(U2-CDBUS3-Pad35)") (class "Default")
      (node (ref "U2") (pin "35") (pinfunction "CDBUS3_35") (pintype "bidirectional"))
    )
    (net (code "101") (name "unconnected-(U2-CDBUS4-Pad37)") (class "Default")
      (node (ref "U2") (pin "37") (pinfunction "CDBUS4_37") (pintype "bidirectional"))
    )
    (net (code "102") (name "unconnected-(U2-CDBUS5-Pad38)") (class "Default")
      (node (ref "U2") (pin "38") (pinfunction "CDBUS5_38") (pintype "bidirectional"))
    )
    (net (code "103") (name "unconnected-(U2-CDBUS6-Pad39)") (class "Default")
      (node (ref "U2") (pin "39") (pinfunction "CDBUS6_39") (pintype "bidirectional"))
    )
    (net (code "104") (name "unconnected-(U2-CDBUS7-Pad40)") (class "Default")
      (node (ref "U2") (pin "40") (pinfunction "CDBUS7_40") (pintype "bidirectional"))
    )
    (net (code "105") (name "unconnected-(U2-DDBUS2-Pad47)") (class "Default")
      (node (ref "U2") (pin "47") (pinfunction "DDBUS2_47") (pintype "bidirectional"))
    )
    (net (code "106") (name "unconnected-(U2-DDBUS3-Pad48)") (class "Default")
      (node (ref "U2") (pin "48") (pinfunction "DDBUS3_48") (pintype "bidirectional"))
    )
    (net (code "107") (name "unconnected-(U2-DDBUS4-Pad49)") (class "Default")
      (node (ref "U2") (pin "49") (pinfunction "DDBUS4_49") (pintype "bidirectional"))
    )
    (net (code "108") (name "unconnected-(U2-DDBUS5-Pad51)") (class "Default")
      (node (ref "U2") (pin "51") (pinfunction "DDBUS5_51") (pintype "bidirectional"))
    )
    (net (code "109") (name "unconnected-(U2-DDBUS6-Pad52)") (class "Default")
      (node (ref "U2") (pin "52") (pinfunction "DDBUS6_52") (pintype "bidirectional"))
    )
    (net (code "110") (name "unconnected-(U2-DDBUS7-Pad53)") (class "Default")
      (node (ref "U2") (pin "53") (pinfunction "DDBUS7_53") (pintype "bidirectional"))
    )
    (net (code "111") (name "unconnected-(U2-~{SUSPEND}-Pad30)") (class "Default")
      (node (ref "U2") (pin "30") (pinfunction "~{SUSPEND}_30") (pintype "output"))
    )
    (net (code "112") (name "unconnected-(U3-3VDDA33-Pad29)") (class "Default")
      (node (ref "U3") (pin "29") (pinfunction "3VDDA33_29") (pintype "output"))
    )
    (net (code "113") (name "unconnected-(U3-CRFILT-Pad14)") (class "Default")
      (node (ref "U3") (pin "14") (pinfunction "CRFILT_14") (pintype "output"))
    )
    (net (code "114") (name "unconnected-(U3-HS_IND{slash}CFG_SEL1-Pad25)") (class "Default")
      (node (ref "U3") (pin "25") (pinfunction "HS_IND/CFG_SEL1_25") (pintype "output"))
    )
    (net (code "115") (name "unconnected-(U3-OCS_N1-Pad13)") (class "Default")
      (node (ref "U3") (pin "13") (pinfunction "OCS_N1_13") (pintype "bidirectional"))
    )
    (net (code "116") (name "unconnected-(U3-OCS_N2-Pad17)") (class "Default")
      (node (ref "U3") (pin "17") (pinfunction "OCS_N2_17") (pintype "bidirectional"))
    )
    (net (code "117") (name "unconnected-(U3-OCS_N3-Pad19)") (class "Default")
      (node (ref "U3") (pin "19") (pinfunction "OCS_N3_19") (pintype "bidirectional"))
    )
    (net (code "118") (name "unconnected-(U3-OCS_N4-Pad21)") (class "Default")
      (node (ref "U3") (pin "21") (pinfunction "OCS_N4_21") (pintype "bidirectional"))
    )
    (net (code "119") (name "unconnected-(U3-PLLFILT-Pad34)") (class "Default")
      (node (ref "U3") (pin "34") (pinfunction "PLLFILT_34") (pintype "output"))
    )
    (net (code "120") (name "unconnected-(U3-PRTPWR1{slash}BC_EN1-Pad12)") (class "Default")
      (node (ref "U3") (pin "12") (pinfunction "PRTPWR1/BC_EN1_12") (pintype "input"))
    )
    (net (code "121") (name "unconnected-(U3-PRTPWR2{slash}BC_EN2-Pad16)") (class "Default")
      (node (ref "U3") (pin "16") (pinfunction "PRTPWR2/BC_EN2_16") (pintype "input"))
    )
    (net (code "122") (name "unconnected-(U3-PRTPWR3{slash}BC_EN3-Pad18)") (class "Default")
      (node (ref "U3") (pin "18") (pinfunction "PRTPWR3/BC_EN3_18") (pintype "input"))
    )
    (net (code "123") (name "unconnected-(U3-PRTPWR4{slash}BC_EN4-Pad20)") (class "Default")
      (node (ref "U3") (pin "20") (pinfunction "PRTPWR4/BC_EN4_20") (pintype "input"))
    )
    (net (code "124") (name "unconnected-(U3-RBIAS-Pad35)") (class "Default")
      (node (ref "U3") (pin "35") (pinfunction "RBIAS_35") (pintype "output"))
    )
    (net (code "125") (name "unconnected-(U3-RESET_N-Pad26)") (class "Default")
      (node (ref "U3") (pin "26") (pinfunction "RESET_N_26") (pintype "input"))
    )
    (net (code "126") (name "unconnected-(U3-SCL{slash}SMBCLK{slash}CFG_SEL0-Pad24)") (class "Default")
      (node (ref "U3") (pin "24") (pinfunction "SCL/SMBCLK/CFG_SEL0_24") (pintype "output"))
    )
    (net (code "127") (name "unconnected-(U3-SDA{slash}SMBDATA{slash}NON_REM1-Pad22)") (class "Default")
      (node (ref "U3") (pin "22") (pinfunction "SDA/SMBDATA/NON_REM1_22") (pintype "bidirectional"))
    )
    (net (code "128") (name "unconnected-(U3-SUSP_IND{slash}LOCAL_PWR{slash}NON_REM0-Pad28)") (class "Default")
      (node (ref "U3") (pin "28") (pinfunction "SUSP_IND/LOCAL_PWR/NON_REM0_28") (pintype "bidirectional"))
    )
    (net (code "129") (name "unconnected-(U3-TEST-Pad11)") (class "Default")
      (node (ref "U3") (pin "11") (pinfunction "TEST_11") (pintype "input"))
    )
    (net (code "130") (name "unconnected-(U3-USBDM_DN1{slash}PRT_DIS_M1-Pad1)") (class "Default")
      (node (ref "U3") (pin "1") (pinfunction "USBDM_DN1/PRT_DIS_M1_1") (pintype "bidirectional"))
    )
    (net (code "131") (name "unconnected-(U3-USBDM_DN2{slash}PRT_DIS_M2-Pad3)") (class "Default")
      (node (ref "U3") (pin "3") (pinfunction "USBDM_DN2/PRT_DIS_M2_3") (pintype "bidirectional"))
    )
    (net (code "132") (name "unconnected-(U3-USBDM_DN3{slash}PRT_DIS_M3-Pad6)") (class "Default")
      (node (ref "U3") (pin "6") (pinfunction "USBDM_DN3/PRT_DIS_M3_6") (pintype "bidirectional"))
    )
    (net (code "133") (name "unconnected-(U3-USBDM_DN4{slash}PRT_DIS_M4-Pad8)") (class "Default")
      (node (ref "U3") (pin "8") (pinfunction "USBDM_DN4/PRT_DIS_M4_8") (pintype "bidirectional"))
    )
    (net (code "134") (name "unconnected-(U3-USBDM_UP-Pad30)") (class "Default")
      (node (ref "U3") (pin "30") (pinfunction "USBDM_UP_30") (pintype "bidirectional"))
    )
    (net (code "135") (name "unconnected-(U3-USBDP_DN1{slash}PRT_DIS_P1-Pad2)") (class "Default")
      (node (ref "U3") (pin "2") (pinfunction "USBDP_DN1/PRT_DIS_P1_2") (pintype "bidirectional"))
    )
    (net (code "136") (name "unconnected-(U3-USBDP_DN2{slash}PRT_DIS_P2-Pad4)") (class "Default")
      (node (ref "U3") (pin "4") (pinfunction "USBDP_DN2/PRT_DIS_P2_4") (pintype "bidirectional"))
    )
    (net (code "137") (name "unconnected-(U3-USBDP_DN3{slash}PRT_DIS_P3-Pad7)") (class "Default")
      (node (ref "U3") (pin "7") (pinfunction "USBDP_DN3/PRT_DIS_P3_7") (pintype "bidirectional"))
    )
    (net (code "138") (name "unconnected-(U3-USBDP_DN4{slash}PRT_DIS_P4-Pad9)") (class "Default")
      (node (ref "U3") (pin "9") (pinfunction "USBDP_DN4/PRT_DIS_P4_9") (pintype "bidirectional"))
    )
    (net (code "139") (name "unconnected-(U3-USBDP_UP-Pad31)") (class "Default")
      (node (ref "U3") (pin "31") (pinfunction "USBDP_UP_31") (pintype "bidirectional"))
    )
    (net (code "140") (name "unconnected-(U3-VBUS_DET-Pad27)") (class "Default")
      (node (ref "U3") (pin "27") (pinfunction "VBUS_DET_27") (pintype "input"))
    )
  )
)
